# AOC_v1.net
KiCad netlist of a schematic drawn in EAGLE
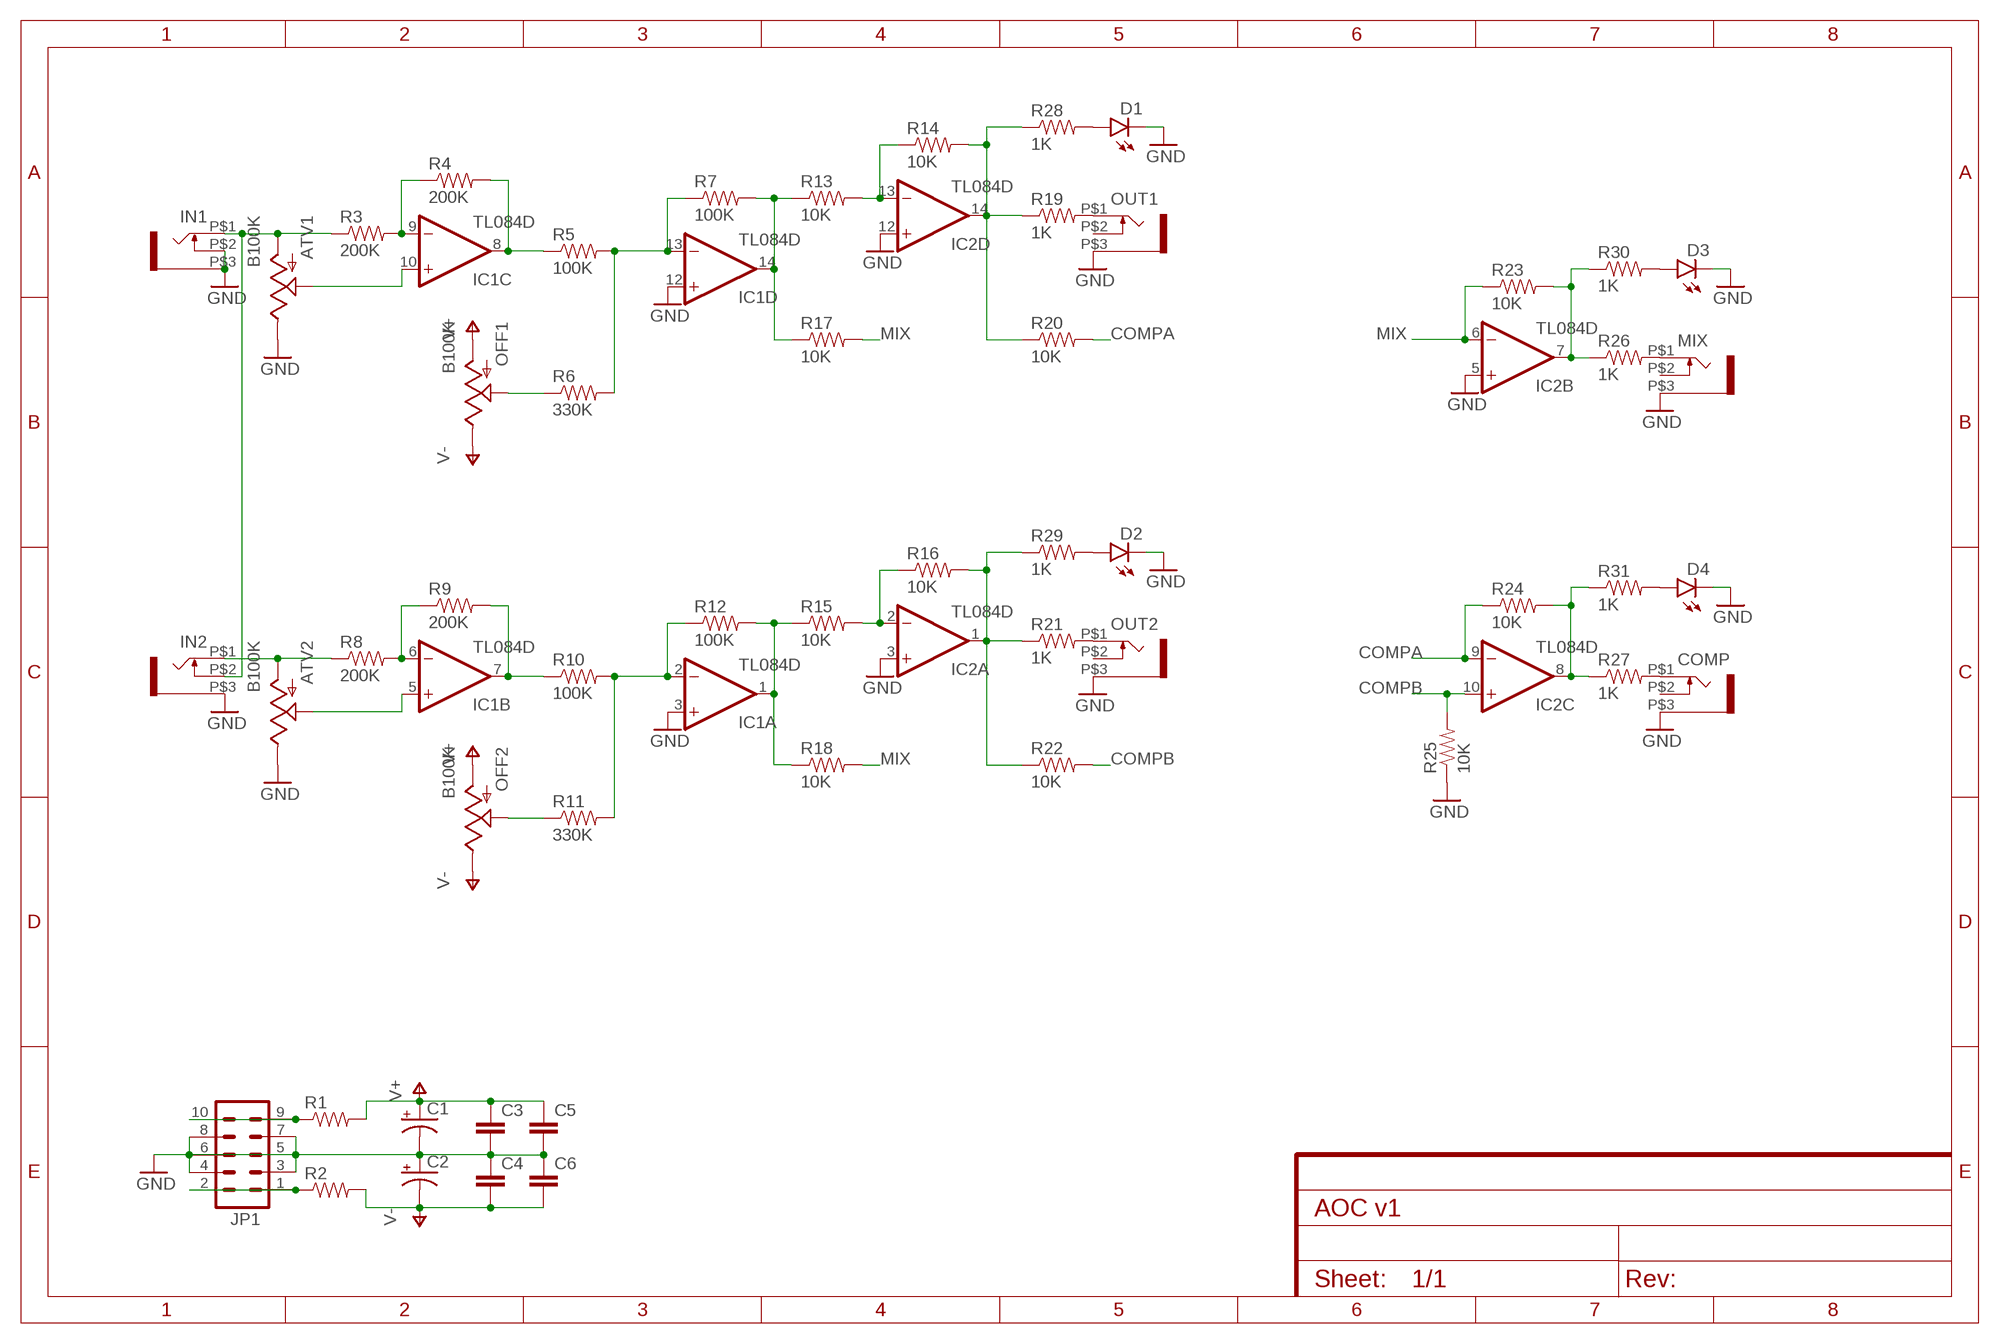
[diagram p0: schematic, sheet 1]

(export (version "E")
  (design (tool "Eeschema 10.0.6"))
  (components
    (comp (ref "ATV1")
      (value "B100K")
      (footprint "eagle-import:ALPS_POT")
      (libsource (lib "eagle-import") (part "POT"))
    )
    (comp (ref "ATV2")
      (value "B100K")
      (footprint "eagle-import:ALPS_POT")
      (libsource (lib "eagle-import") (part "POT"))
    )
    (comp (ref "C1")
      (value "CAP_POLPTH2")
      (footprint "eagle-import:CPOL-RADIAL-10UF-25V")
      (libsource (lib "eagle-import") (part "CAP_POLPTH2"))
    )
    (comp (ref "C2")
      (value "CAP_POLPTH2")
      (footprint "eagle-import:CPOL-RADIAL-10UF-25V")
      (libsource (lib "eagle-import") (part "CAP_POLPTH2"))
    )
    (comp (ref "C3")
      (value "CAP0805")
      (footprint "eagle-import:0805")
      (libsource (lib "eagle-import") (part "CAP0805"))
    )
    (comp (ref "C4")
      (value "CAP0805")
      (footprint "eagle-import:0805")
      (libsource (lib "eagle-import") (part "CAP0805"))
    )
    (comp (ref "C5")
      (value "CAP0805")
      (footprint "eagle-import:0805")
      (libsource (lib "eagle-import") (part "CAP0805"))
    )
    (comp (ref "C6")
      (value "CAP0805")
      (footprint "eagle-import:0805")
      (libsource (lib "eagle-import") (part "CAP0805"))
    )
    (comp (ref "COMP")
      (value "WQP-PJ301M-12_JACK")
      (footprint "eagle-import:WQP-PJ301M-12_JACK")
      (libsource (lib "eagle-import") (part "WQP-PJ301M-12_JACK"))
    )
    (comp (ref "D1")
      (value "LED3MM")
      (footprint "eagle-import:LED3MM")
      (libsource (lib "eagle-import") (part "LED3MM"))
    )
    (comp (ref "D2")
      (value "LED3MM")
      (footprint "eagle-import:LED3MM")
      (libsource (lib "eagle-import") (part "LED3MM"))
    )
    (comp (ref "D3")
      (value "LED3MM")
      (footprint "eagle-import:LED3MM")
      (libsource (lib "eagle-import") (part "LED3MM"))
    )
    (comp (ref "D4")
      (value "LED3MM")
      (footprint "eagle-import:LED3MM")
      (libsource (lib "eagle-import") (part "LED3MM"))
    )
    (comp (ref "IC1")
      (value "TL084D")
      (footprint "eagle-import:SO14")
      (libsource (lib "eagle-import") (part "TL084D"))
    )
    (comp (ref "IC2")
      (value "TL084D")
      (footprint "eagle-import:SO14")
      (libsource (lib "eagle-import") (part "TL084D"))
    )
    (comp (ref "IN1")
      (value "WQP-PJ301M-12_JACK")
      (footprint "eagle-import:WQP-PJ301M-12_JACK")
      (libsource (lib "eagle-import") (part "WQP-PJ301M-12_JACK"))
    )
    (comp (ref "IN2")
      (value "WQP-PJ301M-12_JACK")
      (footprint "eagle-import:WQP-PJ301M-12_JACK")
      (libsource (lib "eagle-import") (part "WQP-PJ301M-12_JACK"))
    )
    (comp (ref "JP1")
      (value "M05X2PTH")
      (footprint "eagle-import:AVR_ICSP")
      (libsource (lib "eagle-import") (part "M05X2PTH"))
    )
    (comp (ref "MIX")
      (value "WQP-PJ301M-12_JACK")
      (footprint "eagle-import:WQP-PJ301M-12_JACK")
      (libsource (lib "eagle-import") (part "WQP-PJ301M-12_JACK"))
    )
    (comp (ref "OFF1")
      (value "B100K")
      (footprint "eagle-import:ALPS_POT")
      (libsource (lib "eagle-import") (part "POT"))
    )
    (comp (ref "OFF2")
      (value "B100K")
      (footprint "eagle-import:ALPS_POT")
      (libsource (lib "eagle-import") (part "POT"))
    )
    (comp (ref "OUT1")
      (value "WQP-PJ301M-12_JACK")
      (footprint "eagle-import:WQP-PJ301M-12_JACK")
      (libsource (lib "eagle-import") (part "WQP-PJ301M-12_JACK"))
    )
    (comp (ref "OUT2")
      (value "WQP-PJ301M-12_JACK")
      (footprint "eagle-import:WQP-PJ301M-12_JACK")
      (libsource (lib "eagle-import") (part "WQP-PJ301M-12_JACK"))
    )
    (comp (ref "R1")
      (value "RESISTOR0805-RES")
      (footprint "eagle-import:0805@1")
      (libsource (lib "eagle-import") (part "RESISTOR0805-RES"))
    )
    (comp (ref "R2")
      (value "RESISTOR0805-RES")
      (footprint "eagle-import:0805@1")
      (libsource (lib "eagle-import") (part "RESISTOR0805-RES"))
    )
    (comp (ref "R3")
      (value "200K")
      (footprint "eagle-import:0805@1")
      (libsource (lib "eagle-import") (part "RESISTOR0805-RES"))
    )
    (comp (ref "R4")
      (value "200K")
      (footprint "eagle-import:0805@1")
      (libsource (lib "eagle-import") (part "RESISTOR0805-RES"))
    )
    (comp (ref "R5")
      (value "100K")
      (footprint "eagle-import:0805@1")
      (libsource (lib "eagle-import") (part "RESISTOR0805-RES"))
    )
    (comp (ref "R6")
      (value "330K")
      (footprint "eagle-import:0805@1")
      (libsource (lib "eagle-import") (part "RESISTOR0805-RES"))
    )
    (comp (ref "R7")
      (value "100K")
      (footprint "eagle-import:0805@1")
      (libsource (lib "eagle-import") (part "RESISTOR0805-RES"))
    )
    (comp (ref "R8")
      (value "200K")
      (footprint "eagle-import:0805@1")
      (libsource (lib "eagle-import") (part "RESISTOR0805-RES"))
    )
    (comp (ref "R9")
      (value "200K")
      (footprint "eagle-import:0805@1")
      (libsource (lib "eagle-import") (part "RESISTOR0805-RES"))
    )
    (comp (ref "R10")
      (value "100K")
      (footprint "eagle-import:0805@1")
      (libsource (lib "eagle-import") (part "RESISTOR0805-RES"))
    )
    (comp (ref "R11")
      (value "330K")
      (footprint "eagle-import:0805@1")
      (libsource (lib "eagle-import") (part "RESISTOR0805-RES"))
    )
    (comp (ref "R12")
      (value "100K")
      (footprint "eagle-import:0805@1")
      (libsource (lib "eagle-import") (part "RESISTOR0805-RES"))
    )
    (comp (ref "R13")
      (value "10K")
      (footprint "eagle-import:0805@1")
      (libsource (lib "eagle-import") (part "RESISTOR0805-RES"))
    )
    (comp (ref "R14")
      (value "10K")
      (footprint "eagle-import:0805@1")
      (libsource (lib "eagle-import") (part "RESISTOR0805-RES"))
    )
    (comp (ref "R15")
      (value "10K")
      (footprint "eagle-import:0805@1")
      (libsource (lib "eagle-import") (part "RESISTOR0805-RES"))
    )
    (comp (ref "R16")
      (value "10K")
      (footprint "eagle-import:0805@1")
      (libsource (lib "eagle-import") (part "RESISTOR0805-RES"))
    )
    (comp (ref "R17")
      (value "10K")
      (footprint "eagle-import:0805@1")
      (libsource (lib "eagle-import") (part "RESISTOR0805-RES"))
    )
    (comp (ref "R18")
      (value "10K")
      (footprint "eagle-import:0805@1")
      (libsource (lib "eagle-import") (part "RESISTOR0805-RES"))
    )
    (comp (ref "R19")
      (value "1K")
      (footprint "eagle-import:0805@1")
      (libsource (lib "eagle-import") (part "RESISTOR0805-RES"))
    )
    (comp (ref "R20")
      (value "10K")
      (footprint "eagle-import:0805@1")
      (libsource (lib "eagle-import") (part "RESISTOR0805-RES"))
    )
    (comp (ref "R21")
      (value "1K")
      (footprint "eagle-import:0805@1")
      (libsource (lib "eagle-import") (part "RESISTOR0805-RES"))
    )
    (comp (ref "R22")
      (value "10K")
      (footprint "eagle-import:0805@1")
      (libsource (lib "eagle-import") (part "RESISTOR0805-RES"))
    )
    (comp (ref "R23")
      (value "10K")
      (footprint "eagle-import:0805@1")
      (libsource (lib "eagle-import") (part "RESISTOR0805-RES"))
    )
    (comp (ref "R24")
      (value "10K")
      (footprint "eagle-import:0805@1")
      (libsource (lib "eagle-import") (part "RESISTOR0805-RES"))
    )
    (comp (ref "R25")
      (value "10K")
      (footprint "eagle-import:0805@1")
      (libsource (lib "eagle-import") (part "RESISTOR0805-RES"))
    )
    (comp (ref "R26")
      (value "1K")
      (footprint "eagle-import:0805@1")
      (libsource (lib "eagle-import") (part "RESISTOR0805-RES"))
    )
    (comp (ref "R27")
      (value "1K")
      (footprint "eagle-import:0805@1")
      (libsource (lib "eagle-import") (part "RESISTOR0805-RES"))
    )
    (comp (ref "R28")
      (value "1K")
      (footprint "eagle-import:0805@1")
      (libsource (lib "eagle-import") (part "RESISTOR0805-RES"))
    )
    (comp (ref "R29")
      (value "1K")
      (footprint "eagle-import:0805@1")
      (libsource (lib "eagle-import") (part "RESISTOR0805-RES"))
    )
    (comp (ref "R30")
      (value "1K")
      (footprint "eagle-import:0805@1")
      (libsource (lib "eagle-import") (part "RESISTOR0805-RES"))
    )
    (comp (ref "R31")
      (value "1K")
      (footprint "eagle-import:0805@1")
      (libsource (lib "eagle-import") (part "RESISTOR0805-RES"))
    )
  )
  (nets
    (net (code "1") (name "/COMPA") (class "Default")
      (node (ref "IC2") (pin "9") (pinfunction "-IN_9") (pintype "input"))
      (node (ref "R20") (pin "2") (pinfunction "2_2") (pintype "passive"))
      (node (ref "R24") (pin "1") (pinfunction "1_1") (pintype "passive"))
    )
    (net (code "2") (name "/COMPB") (class "Default")
      (node (ref "IC2") (pin "10") (pinfunction "+IN_10") (pintype "input"))
      (node (ref "R22") (pin "2") (pinfunction "2_2") (pintype "passive"))
      (node (ref "R25") (pin "2") (pinfunction "2_2") (pintype "passive"))
    )
    (net (code "3") (name "/MIX") (class "Default")
      (node (ref "IC2") (pin "6") (pinfunction "-IN_6") (pintype "input"))
      (node (ref "R17") (pin "2") (pinfunction "2_2") (pintype "passive"))
      (node (ref "R18") (pin "2") (pinfunction "2_2") (pintype "passive"))
      (node (ref "R23") (pin "1") (pinfunction "1_1") (pintype "passive"))
    )
    (net (code "4") (name "GND") (class "Default")
      (node (ref "ATV1") (pin "P$1") (pinfunction "E_P$1") (pintype "passive"))
      (node (ref "ATV2") (pin "P$1") (pinfunction "E_P$1") (pintype "passive"))
      (node (ref "C1") (pin "2") (pinfunction "-_2") (pintype "passive"))
      (node (ref "C2") (pin "1") (pinfunction "+_1") (pintype "passive"))
      (node (ref "C3") (pin "2") (pinfunction "2_2") (pintype "passive"))
      (node (ref "C4") (pin "1") (pinfunction "1_1") (pintype "passive"))
      (node (ref "C5") (pin "2") (pinfunction "2_2") (pintype "passive"))
      (node (ref "C6") (pin "1") (pinfunction "1_1") (pintype "passive"))
      (node (ref "COMP") (pin "P$3") (pinfunction "1_P$3") (pintype "passive"))
      (node (ref "D1") (pin "K") (pinfunction "C_K") (pintype "passive"))
      (node (ref "D2") (pin "K") (pinfunction "C_K") (pintype "passive"))
      (node (ref "D3") (pin "K") (pinfunction "C_K") (pintype "passive"))
      (node (ref "D4") (pin "K") (pinfunction "C_K") (pintype "passive"))
      (node (ref "IC1") (pin "12") (pinfunction "+IN_12") (pintype "input"))
      (node (ref "IC1") (pin "3") (pinfunction "+IN_3") (pintype "input"))
      (node (ref "IC2") (pin "12") (pinfunction "+IN_12") (pintype "input"))
      (node (ref "IC2") (pin "3") (pinfunction "+IN_3") (pintype "input"))
      (node (ref "IC2") (pin "5") (pinfunction "+IN_5") (pintype "input"))
      (node (ref "IN1") (pin "P$2") (pinfunction "3_P$2") (pintype "passive"))
      (node (ref "IN1") (pin "P$3") (pinfunction "1_P$3") (pintype "passive"))
      (node (ref "IN2") (pin "P$3") (pinfunction "1_P$3") (pintype "passive"))
      (node (ref "JP1") (pin "3") (pinfunction "3_3") (pintype "passive"))
      (node (ref "JP1") (pin "4") (pinfunction "4_4") (pintype "passive"))
      (node (ref "JP1") (pin "5") (pinfunction "5_5") (pintype "passive"))
      (node (ref "JP1") (pin "6") (pinfunction "6_6") (pintype "passive"))
      (node (ref "JP1") (pin "7") (pinfunction "7_7") (pintype "passive"))
      (node (ref "JP1") (pin "8") (pinfunction "8_8") (pintype "passive"))
      (node (ref "MIX") (pin "P$3") (pinfunction "1_P$3") (pintype "passive"))
      (node (ref "OUT1") (pin "P$3") (pinfunction "1_P$3") (pintype "passive"))
      (node (ref "OUT2") (pin "P$3") (pinfunction "1_P$3") (pintype "passive"))
      (node (ref "R25") (pin "1") (pinfunction "1_1") (pintype "passive"))
    )
    (net (code "5") (name "Net-(ATV1-A)") (class "Default")
      (node (ref "ATV1") (pin "P$3") (pinfunction "A_P$3") (pintype "passive"))
      (node (ref "IN1") (pin "P$1") (pinfunction "2_P$1") (pintype "passive"))
      (node (ref "IN2") (pin "P$2") (pinfunction "3_P$2") (pintype "passive"))
      (node (ref "R3") (pin "1") (pinfunction "1_1") (pintype "passive"))
    )
    (net (code "6") (name "Net-(ATV1-S)") (class "Default")
      (node (ref "ATV1") (pin "P$2") (pinfunction "S_P$2") (pintype "passive"))
      (node (ref "IC1") (pin "10") (pinfunction "+IN_10") (pintype "input"))
    )
    (net (code "7") (name "Net-(ATV2-A)") (class "Default")
      (node (ref "ATV2") (pin "P$3") (pinfunction "A_P$3") (pintype "passive"))
      (node (ref "IN2") (pin "P$1") (pinfunction "2_P$1") (pintype "passive"))
      (node (ref "R8") (pin "1") (pinfunction "1_1") (pintype "passive"))
    )
    (net (code "8") (name "Net-(ATV2-S)") (class "Default")
      (node (ref "ATV2") (pin "P$2") (pinfunction "S_P$2") (pintype "passive"))
      (node (ref "IC1") (pin "5") (pinfunction "+IN_5") (pintype "input"))
    )
    (net (code "9") (name "Net-(COMP-2)") (class "Default")
      (node (ref "COMP") (pin "P$1") (pinfunction "2_P$1") (pintype "passive"))
      (node (ref "R27") (pin "2") (pinfunction "2_2") (pintype "passive"))
    )
    (net (code "10") (name "Net-(D1-PadA)") (class "Default")
      (node (ref "D1") (pin "A") (pinfunction "A_A") (pintype "passive"))
      (node (ref "R28") (pin "2") (pinfunction "2_2") (pintype "passive"))
    )
    (net (code "11") (name "Net-(D2-PadA)") (class "Default")
      (node (ref "D2") (pin "A") (pinfunction "A_A") (pintype "passive"))
      (node (ref "R29") (pin "2") (pinfunction "2_2") (pintype "passive"))
    )
    (net (code "12") (name "Net-(D3-PadA)") (class "Default")
      (node (ref "D3") (pin "A") (pinfunction "A_A") (pintype "passive"))
      (node (ref "R30") (pin "2") (pinfunction "2_2") (pintype "passive"))
    )
    (net (code "13") (name "Net-(D4-PadA)") (class "Default")
      (node (ref "D4") (pin "A") (pinfunction "A_A") (pintype "passive"))
      (node (ref "R31") (pin "2") (pinfunction "2_2") (pintype "passive"))
    )
    (net (code "14") (name "Net-(IC1A--IN)") (class "Default")
      (node (ref "IC1") (pin "2") (pinfunction "-IN_2") (pintype "input"))
      (node (ref "R10") (pin "2") (pinfunction "2_2") (pintype "passive"))
      (node (ref "R11") (pin "2") (pinfunction "2_2") (pintype "passive"))
      (node (ref "R12") (pin "1") (pinfunction "1_1") (pintype "passive"))
    )
    (net (code "15") (name "Net-(IC1A-OUT)") (class "Default")
      (node (ref "IC1") (pin "1") (pinfunction "OUT_1") (pintype "output"))
      (node (ref "R12") (pin "2") (pinfunction "2_2") (pintype "passive"))
      (node (ref "R15") (pin "1") (pinfunction "1_1") (pintype "passive"))
      (node (ref "R18") (pin "1") (pinfunction "1_1") (pintype "passive"))
    )
    (net (code "16") (name "Net-(IC1B--IN)") (class "Default")
      (node (ref "IC1") (pin "6") (pinfunction "-IN_6") (pintype "input"))
      (node (ref "R8") (pin "2") (pinfunction "2_2") (pintype "passive"))
      (node (ref "R9") (pin "1") (pinfunction "1_1") (pintype "passive"))
    )
    (net (code "17") (name "Net-(IC1B-OUT)") (class "Default")
      (node (ref "IC1") (pin "7") (pinfunction "OUT_7") (pintype "output"))
      (node (ref "R10") (pin "1") (pinfunction "1_1") (pintype "passive"))
      (node (ref "R9") (pin "2") (pinfunction "2_2") (pintype "passive"))
    )
    (net (code "18") (name "Net-(IC1C--IN)") (class "Default")
      (node (ref "IC1") (pin "9") (pinfunction "-IN_9") (pintype "input"))
      (node (ref "R3") (pin "2") (pinfunction "2_2") (pintype "passive"))
      (node (ref "R4") (pin "1") (pinfunction "1_1") (pintype "passive"))
    )
    (net (code "19") (name "Net-(IC1C-OUT)") (class "Default")
      (node (ref "IC1") (pin "8") (pinfunction "OUT_8") (pintype "output"))
      (node (ref "R4") (pin "2") (pinfunction "2_2") (pintype "passive"))
      (node (ref "R5") (pin "1") (pinfunction "1_1") (pintype "passive"))
    )
    (net (code "20") (name "Net-(IC1D--IN)") (class "Default")
      (node (ref "IC1") (pin "13") (pinfunction "-IN_13") (pintype "input"))
      (node (ref "R5") (pin "2") (pinfunction "2_2") (pintype "passive"))
      (node (ref "R6") (pin "2") (pinfunction "2_2") (pintype "passive"))
      (node (ref "R7") (pin "1") (pinfunction "1_1") (pintype "passive"))
    )
    (net (code "21") (name "Net-(IC1D-OUT)") (class "Default")
      (node (ref "IC1") (pin "14") (pinfunction "OUT_14") (pintype "output"))
      (node (ref "R13") (pin "1") (pinfunction "1_1") (pintype "passive"))
      (node (ref "R17") (pin "1") (pinfunction "1_1") (pintype "passive"))
      (node (ref "R7") (pin "2") (pinfunction "2_2") (pintype "passive"))
    )
    (net (code "22") (name "Net-(IC2A--IN)") (class "Default")
      (node (ref "IC2") (pin "2") (pinfunction "-IN_2") (pintype "input"))
      (node (ref "R15") (pin "2") (pinfunction "2_2") (pintype "passive"))
      (node (ref "R16") (pin "1") (pinfunction "1_1") (pintype "passive"))
    )
    (net (code "23") (name "Net-(IC2A-OUT)") (class "Default")
      (node (ref "IC2") (pin "1") (pinfunction "OUT_1") (pintype "output"))
      (node (ref "R16") (pin "2") (pinfunction "2_2") (pintype "passive"))
      (node (ref "R21") (pin "1") (pinfunction "1_1") (pintype "passive"))
      (node (ref "R22") (pin "1") (pinfunction "1_1") (pintype "passive"))
      (node (ref "R29") (pin "1") (pinfunction "1_1") (pintype "passive"))
    )
    (net (code "24") (name "Net-(IC2B-OUT)") (class "Default")
      (node (ref "IC2") (pin "7") (pinfunction "OUT_7") (pintype "output"))
      (node (ref "R23") (pin "2") (pinfunction "2_2") (pintype "passive"))
      (node (ref "R26") (pin "1") (pinfunction "1_1") (pintype "passive"))
      (node (ref "R30") (pin "1") (pinfunction "1_1") (pintype "passive"))
    )
    (net (code "25") (name "Net-(IC2C-OUT)") (class "Default")
      (node (ref "IC2") (pin "8") (pinfunction "OUT_8") (pintype "output"))
      (node (ref "R24") (pin "2") (pinfunction "2_2") (pintype "passive"))
      (node (ref "R27") (pin "1") (pinfunction "1_1") (pintype "passive"))
      (node (ref "R31") (pin "1") (pinfunction "1_1") (pintype "passive"))
    )
    (net (code "26") (name "Net-(IC2D--IN)") (class "Default")
      (node (ref "IC2") (pin "13") (pinfunction "-IN_13") (pintype "input"))
      (node (ref "R13") (pin "2") (pinfunction "2_2") (pintype "passive"))
      (node (ref "R14") (pin "1") (pinfunction "1_1") (pintype "passive"))
    )
    (net (code "27") (name "Net-(IC2D-OUT)") (class "Default")
      (node (ref "IC2") (pin "14") (pinfunction "OUT_14") (pintype "output"))
      (node (ref "R14") (pin "2") (pinfunction "2_2") (pintype "passive"))
      (node (ref "R19") (pin "1") (pinfunction "1_1") (pintype "passive"))
      (node (ref "R20") (pin "1") (pinfunction "1_1") (pintype "passive"))
      (node (ref "R28") (pin "1") (pinfunction "1_1") (pintype "passive"))
    )
    (net (code "28") (name "Net-(JP1-Pad1)") (class "Default")
      (node (ref "JP1") (pin "1") (pinfunction "1_1") (pintype "passive"))
      (node (ref "JP1") (pin "2") (pinfunction "2_2") (pintype "passive"))
      (node (ref "R2") (pin "1") (pinfunction "1_1") (pintype "passive"))
    )
    (net (code "29") (name "Net-(JP1-Pad10)") (class "Default")
      (node (ref "JP1") (pin "10") (pinfunction "10_10") (pintype "passive"))
      (node (ref "JP1") (pin "9") (pinfunction "9_9") (pintype "passive"))
      (node (ref "R1") (pin "1") (pinfunction "1_1") (pintype "passive"))
    )
    (net (code "30") (name "Net-(MIX-2)") (class "Default")
      (node (ref "MIX") (pin "P$1") (pinfunction "2_P$1") (pintype "passive"))
      (node (ref "R26") (pin "2") (pinfunction "2_2") (pintype "passive"))
    )
    (net (code "31") (name "Net-(OFF1-S)") (class "Default")
      (node (ref "OFF1") (pin "P$2") (pinfunction "S_P$2") (pintype "passive"))
      (node (ref "R6") (pin "1") (pinfunction "1_1") (pintype "passive"))
    )
    (net (code "32") (name "Net-(OFF2-S)") (class "Default")
      (node (ref "OFF2") (pin "P$2") (pinfunction "S_P$2") (pintype "passive"))
      (node (ref "R11") (pin "1") (pinfunction "1_1") (pintype "passive"))
    )
    (net (code "33") (name "Net-(OUT1-2)") (class "Default")
      (node (ref "OUT1") (pin "P$1") (pinfunction "2_P$1") (pintype "passive"))
      (node (ref "R19") (pin "2") (pinfunction "2_2") (pintype "passive"))
    )
    (net (code "34") (name "Net-(OUT2-2)") (class "Default")
      (node (ref "OUT2") (pin "P$1") (pinfunction "2_P$1") (pintype "passive"))
      (node (ref "R21") (pin "2") (pinfunction "2_2") (pintype "passive"))
    )
    (net (code "35") (name "V+") (class "Default")
      (node (ref "C1") (pin "1") (pinfunction "+_1") (pintype "passive"))
      (node (ref "C3") (pin "1") (pinfunction "1_1") (pintype "passive"))
      (node (ref "C5") (pin "1") (pinfunction "1_1") (pintype "passive"))
      (node (ref "OFF1") (pin "P$3") (pinfunction "A_P$3") (pintype "passive"))
      (node (ref "OFF2") (pin "P$3") (pinfunction "A_P$3") (pintype "passive"))
      (node (ref "R1") (pin "2") (pinfunction "2_2") (pintype "passive"))
    )
    (net (code "36") (name "V-") (class "Default")
      (node (ref "C2") (pin "2") (pinfunction "-_2") (pintype "passive"))
      (node (ref "C4") (pin "2") (pinfunction "2_2") (pintype "passive"))
      (node (ref "C6") (pin "2") (pinfunction "2_2") (pintype "passive"))
      (node (ref "OFF1") (pin "P$1") (pinfunction "E_P$1") (pintype "passive"))
      (node (ref "OFF2") (pin "P$1") (pinfunction "E_P$1") (pintype "passive"))
      (node (ref "R2") (pin "2") (pinfunction "2_2") (pintype "passive"))
    )
    (net (code "37") (name "unconnected-(COMP-3-PadP$2)") (class "Default")
      (node (ref "COMP") (pin "P$2") (pinfunction "3_P$2") (pintype "passive"))
    )
    (net (code "38") (name "unconnected-(MIX-3-PadP$2)") (class "Default")
      (node (ref "MIX") (pin "P$2") (pinfunction "3_P$2") (pintype "passive"))
    )
    (net (code "39") (name "unconnected-(OUT1-3-PadP$2)") (class "Default")
      (node (ref "OUT1") (pin "P$2") (pinfunction "3_P$2") (pintype "passive"))
    )
    (net (code "40") (name "unconnected-(OUT2-3-PadP$2)") (class "Default")
      (node (ref "OUT2") (pin "P$2") (pinfunction "3_P$2") (pintype "passive"))
    )
  )
)
